# SmartMatrixSD_V1.net
KiCad netlist of a schematic drawn in EAGLE
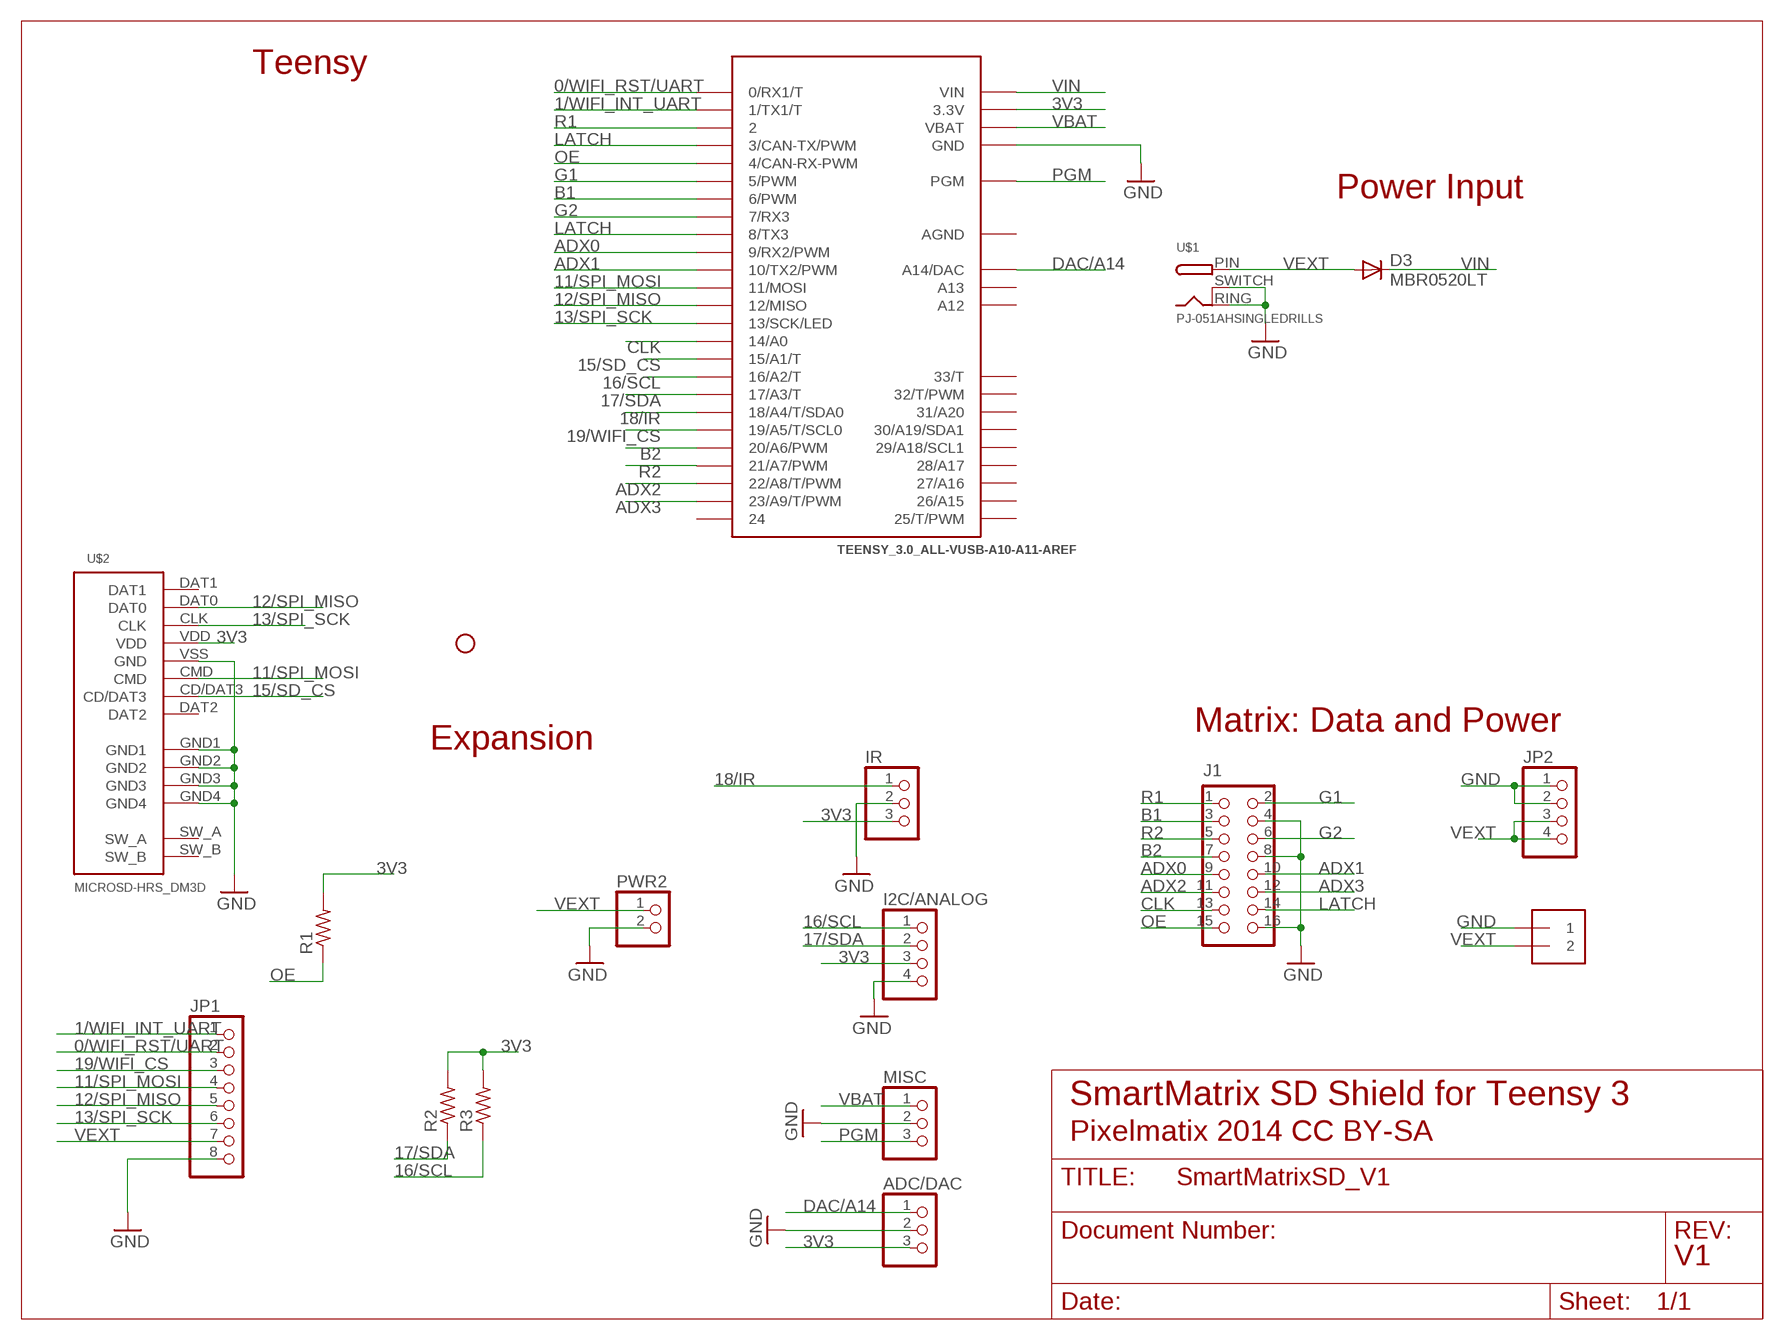
[diagram p0: schematic, sheet 1]

(export (version "E")
  (design (tool "Eeschema 10.0.6"))
  (components
    (comp (ref "ADC/DAC")
      (value "PINHD-1X03_2.54-S")
      (footprint "eagle-import:1X03-S")
      (libsource (lib "eagle-import") (part "PINHD-1X03_2.54-S"))
    )
    (comp (ref "D3")
      (value "MBR0520LT")
      (footprint "eagle-import:SOD123")
      (libsource (lib "eagle-import") (part "MBR0520LT"))
    )
    (comp (ref "I2C/ANALOG")
      (value "PINHD-1X04_2.54-S")
      (footprint "eagle-import:1X04-S")
      (libsource (lib "eagle-import") (part "pinhead-2_PINHD-1X04_2.54-S"))
    )
    (comp (ref "IR")
      (value "PINHD-1X03_2.54-S")
      (footprint "eagle-import:1X03-S")
      (libsource (lib "eagle-import") (part "PINHD-1X03_2.54-S"))
    )
    (comp (ref "J1")
      (value "CON_HEADER_2X08-PTH-SHROUDED")
      (footprint "eagle-import:PINSHRD_PTH_2X08")
      (libsource (lib "eagle-import") (part "CON_HEADER_2X08-PTH-SHROUDED"))
    )
    (comp (ref "J4")
      (value "1X2-5.0")
      (footprint "eagle-import:1X2-5.0MM")
      (libsource (lib "eagle-import") (part "1X2-5.0"))
    )
    (comp (ref "JP1")
      (value "PINHD-1X08_2.54-S")
      (footprint "eagle-import:1X08-S")
      (libsource (lib "eagle-import") (part "PINHD-1X08_2.54-S"))
    )
    (comp (ref "JP2")
      (value "PINHD-1X04_1.56")
      (footprint "eagle-import:1X04-1.56_")
      (libsource (lib "eagle-import") (part "PINHD-1X04_1.56"))
    )
    (comp (ref "JP5")
      (value "STAND-OFFSTAND-OFF-3MM")
      (footprint "eagle-import:STAND-OFF-3MM")
      (libsource (lib "eagle-import") (part "STAND-OFFSTAND-OFF-3MM"))
    )
    (comp (ref "MISC")
      (value "PINHD-1X03_2.54-S")
      (footprint "eagle-import:1X03-S")
      (libsource (lib "eagle-import") (part "PINHD-1X03_2.54-S"))
    )
    (comp (ref "PWR2")
      (value "PINHD-1X02_2.54-S")
      (footprint "eagle-import:1X02-S")
      (libsource (lib "eagle-import") (part "PINHD-1X02_2.54-S"))
    )
    (comp (ref "R1")
      (value "R-US_R0603")
      (footprint "eagle-import:R0603")
      (libsource (lib "eagle-import") (part "R-US_R0603"))
    )
    (comp (ref "R2")
      (value "R-US_0207/7")
      (footprint "eagle-import:0207_7")
      (libsource (lib "eagle-import") (part "R-US_0207/7"))
    )
    (comp (ref "R3")
      (value "R-US_0207/7")
      (footprint "eagle-import:0207_7")
      (libsource (lib "eagle-import") (part "R-US_0207/7"))
    )
    (comp (ref "U$1")
      (value "PJ-051AHSINGLEDRILLS")
      (footprint "eagle-import:PJ-051AH-SINGLEDRILLS")
      (libsource (lib "eagle-import") (part "PJ-051AHSINGLEDRILLS"))
    )
    (comp (ref "U$2")
      (value "MICROSD-HRS_DM3D")
      (footprint "eagle-import:DM3D")
      (libsource (lib "eagle-import") (part "MICROSD-HRS_DM3D"))
    )
    (comp (ref "U$3")
      (value "TEENSY_3.0_ALL-VUSB-A10-A11-AREF")
      (footprint "eagle-import:TEENSY_3.0_ALLPINS-VUSB-A11-A10-AREF")
      (libsource (lib "eagle-import") (part "TEENSY_3.0_ALL-VUSB-A10-A11-AREF"))
    )
  )
  (nets
    (net (code "1") (name "/0{slash}WIFI_RST{slash}UART") (class "Default")
      (node (ref "JP1") (pin "2") (pinfunction "2_2") (pintype "passive"))
      (node (ref "U$3") (pin "0") (pinfunction "0/RX1/T_0") (pintype "bidirectional"))
    )
    (net (code "2") (name "/1{slash}WIFI_INT_UART") (class "Default")
      (node (ref "JP1") (pin "1") (pinfunction "1_1") (pintype "passive"))
      (node (ref "U$3") (pin "1") (pinfunction "1/TX1/T_1") (pintype "bidirectional"))
    )
    (net (code "3") (name "/3V3") (class "Default")
      (node (ref "ADC/DAC") (pin "3") (pinfunction "3_3") (pintype "passive"))
      (node (ref "I2C/ANALOG") (pin "3") (pinfunction "3_3") (pintype "passive"))
      (node (ref "IR") (pin "3") (pinfunction "3_3") (pintype "passive"))
      (node (ref "R1") (pin "2") (pinfunction "2_2") (pintype "passive"))
      (node (ref "R2") (pin "2") (pinfunction "2_2") (pintype "passive"))
      (node (ref "R3") (pin "2") (pinfunction "2_2") (pintype "passive"))
      (node (ref "U$2") (pin "VDD") (pinfunction "VDD_VDD") (pintype "bidirectional"))
      (node (ref "U$3") (pin "3.3V") (pinfunction "3.3V_3.3V") (pintype "power_in"))
      (node (ref "U$3") (pin "3.3V1") (pinfunction "3.3V_3.3V1") (pintype "power_in"))
      (node (ref "U$3") (pin "3.3V2") (pinfunction "3.3V_3.3V2") (pintype "power_in"))
    )
    (net (code "4") (name "/11{slash}SPI_MOSI") (class "Default")
      (node (ref "JP1") (pin "4") (pinfunction "4_4") (pintype "passive"))
      (node (ref "U$2") (pin "CMD") (pinfunction "CMD_CMD") (pintype "bidirectional"))
      (node (ref "U$3") (pin "11") (pinfunction "11/MOSI_11") (pintype "bidirectional"))
    )
    (net (code "5") (name "/12{slash}SPI_MISO") (class "Default")
      (node (ref "JP1") (pin "5") (pinfunction "5_5") (pintype "passive"))
      (node (ref "U$2") (pin "DAT0") (pinfunction "DAT0_DAT0") (pintype "bidirectional"))
      (node (ref "U$3") (pin "12") (pinfunction "12/MISO_12") (pintype "bidirectional"))
    )
    (net (code "6") (name "/13{slash}SPI_SCK") (class "Default")
      (node (ref "JP1") (pin "6") (pinfunction "6_6") (pintype "passive"))
      (node (ref "U$2") (pin "CLK") (pinfunction "CLK_CLK") (pintype "bidirectional"))
      (node (ref "U$3") (pin "13") (pinfunction "13/SCK/LED_13") (pintype "bidirectional"))
    )
    (net (code "7") (name "/15{slash}SD_CS") (class "Default")
      (node (ref "U$2") (pin "CD/DAT3") (pinfunction "CD/DAT3_CD/DAT3") (pintype "bidirectional"))
      (node (ref "U$3") (pin "15/A1") (pinfunction "15/A1/T_15/A1") (pintype "bidirectional"))
    )
    (net (code "8") (name "/16{slash}SCL") (class "Default")
      (node (ref "I2C/ANALOG") (pin "1") (pinfunction "1_1") (pintype "passive"))
      (node (ref "R3") (pin "1") (pinfunction "1_1") (pintype "passive"))
      (node (ref "U$3") (pin "16/A2") (pinfunction "16/A2/T_16/A2") (pintype "bidirectional"))
    )
    (net (code "9") (name "/17{slash}SDA") (class "Default")
      (node (ref "I2C/ANALOG") (pin "2") (pinfunction "2_2") (pintype "passive"))
      (node (ref "R2") (pin "1") (pinfunction "1_1") (pintype "passive"))
      (node (ref "U$3") (pin "17/A3") (pinfunction "17/A3/T_17/A3") (pintype "bidirectional"))
    )
    (net (code "10") (name "/18{slash}IR") (class "Default")
      (node (ref "IR") (pin "1") (pinfunction "1_1") (pintype "passive"))
      (node (ref "U$3") (pin "18/A4") (pinfunction "18/A4/T/SDA0_18/A4") (pintype "bidirectional"))
    )
    (net (code "11") (name "/19{slash}WIFI_CS") (class "Default")
      (node (ref "JP1") (pin "3") (pinfunction "3_3") (pintype "passive"))
      (node (ref "U$3") (pin "19/A5") (pinfunction "19/A5/T/SCL0_19/A5") (pintype "bidirectional"))
    )
    (net (code "12") (name "/ADX0") (class "Default")
      (node (ref "J1") (pin "9") (pinfunction "9_9") (pintype "passive"))
      (node (ref "U$3") (pin "9") (pinfunction "9/RX2/PWM_9") (pintype "bidirectional"))
    )
    (net (code "13") (name "/ADX1") (class "Default")
      (node (ref "J1") (pin "10") (pinfunction "10_10") (pintype "passive"))
      (node (ref "U$3") (pin "10") (pinfunction "10/TX2/PWM_10") (pintype "bidirectional"))
    )
    (net (code "14") (name "/ADX2") (class "Default")
      (node (ref "J1") (pin "11") (pinfunction "11_11") (pintype "passive"))
      (node (ref "U$3") (pin "22/A8") (pinfunction "22/A8/T/PWM_22/A8") (pintype "bidirectional"))
    )
    (net (code "15") (name "/ADX3") (class "Default")
      (node (ref "J1") (pin "12") (pinfunction "12_12") (pintype "passive"))
      (node (ref "U$3") (pin "23/A9") (pinfunction "23/A9/T/PWM_23/A9") (pintype "bidirectional"))
    )
    (net (code "16") (name "/AGND") (class "Default")
      (node (ref "U$3") (pin "AGND") (pinfunction "AGND_AGND") (pintype "power_in"))
    )
    (net (code "17") (name "/B1") (class "Default")
      (node (ref "J1") (pin "3") (pinfunction "3_3") (pintype "passive"))
      (node (ref "U$3") (pin "6") (pinfunction "6/PWM_6") (pintype "bidirectional"))
    )
    (net (code "18") (name "/B2") (class "Default")
      (node (ref "J1") (pin "7") (pinfunction "7_7") (pintype "passive"))
      (node (ref "U$3") (pin "20/A6") (pinfunction "20/A6/PWM_20/A6") (pintype "bidirectional"))
    )
    (net (code "19") (name "/CLK") (class "Default")
      (node (ref "J1") (pin "13") (pinfunction "13_13") (pintype "passive"))
      (node (ref "U$3") (pin "14/A0") (pinfunction "14/A0_14/A0") (pintype "bidirectional"))
    )
    (net (code "20") (name "/DAC{slash}A14") (class "Default")
      (node (ref "ADC/DAC") (pin "1") (pinfunction "1_1") (pintype "passive"))
      (node (ref "U$3") (pin "RESET") (pinfunction "A14/DAC_RESET") (pintype "bidirectional"))
    )
    (net (code "21") (name "/G1") (class "Default")
      (node (ref "J1") (pin "2") (pinfunction "2_2") (pintype "passive"))
      (node (ref "U$3") (pin "5") (pinfunction "5/PWM_5") (pintype "bidirectional"))
    )
    (net (code "22") (name "/G2") (class "Default")
      (node (ref "J1") (pin "6") (pinfunction "6_6") (pintype "passive"))
      (node (ref "U$3") (pin "7") (pinfunction "7/RX3_7") (pintype "bidirectional"))
    )
    (net (code "23") (name "/LATCH") (class "Default")
      (node (ref "J1") (pin "14") (pinfunction "14_14") (pintype "passive"))
      (node (ref "U$3") (pin "3") (pinfunction "3/CAN-TX/PWM_3") (pintype "bidirectional"))
      (node (ref "U$3") (pin "8") (pinfunction "8/TX3_8") (pintype "bidirectional"))
    )
    (net (code "24") (name "/OE") (class "Default")
      (node (ref "J1") (pin "15") (pinfunction "15_15") (pintype "passive"))
      (node (ref "R1") (pin "1") (pinfunction "1_1") (pintype "passive"))
      (node (ref "U$3") (pin "4") (pinfunction "4/CAN-RX-PWM_4") (pintype "bidirectional"))
    )
    (net (code "25") (name "/PGM") (class "Default")
      (node (ref "MISC") (pin "3") (pinfunction "3_3") (pintype "passive"))
      (node (ref "U$3") (pin "PGM") (pinfunction "PGM_PGM") (pintype "bidirectional"))
    )
    (net (code "26") (name "/R1") (class "Default")
      (node (ref "J1") (pin "1") (pinfunction "1_1") (pintype "passive"))
      (node (ref "U$3") (pin "2") (pinfunction "2_2") (pintype "bidirectional"))
    )
    (net (code "27") (name "/R2") (class "Default")
      (node (ref "J1") (pin "5") (pinfunction "5_5") (pintype "passive"))
      (node (ref "U$3") (pin "21/A7") (pinfunction "21/A7/PWM_21/A7") (pintype "bidirectional"))
    )
    (net (code "28") (name "/VBAT") (class "Default")
      (node (ref "MISC") (pin "1") (pinfunction "1_1") (pintype "passive"))
      (node (ref "U$3") (pin "VBAT") (pinfunction "VBAT_VBAT") (pintype "power_in"))
    )
    (net (code "29") (name "/VEXT") (class "Default")
      (node (ref "D3") (pin "A") (pinfunction "A_A") (pintype "passive"))
      (node (ref "J4") (pin "2") (pinfunction "2_2") (pintype "passive"))
      (node (ref "JP1") (pin "7") (pinfunction "7_7") (pintype "passive"))
      (node (ref "JP2") (pin "3") (pinfunction "3_3") (pintype "passive"))
      (node (ref "JP2") (pin "4") (pinfunction "4_4") (pintype "passive"))
      (node (ref "PWR2") (pin "1") (pinfunction "1_1") (pintype "passive"))
      (node (ref "U$1") (pin "PIN") (pinfunction "PWR_PIN") (pintype "power_in"))
    )
    (net (code "30") (name "/VIN") (class "Default")
      (node (ref "D3") (pin "C") (pinfunction "C_C") (pintype "passive"))
      (node (ref "U$3") (pin "VIN") (pinfunction "VIN_VIN") (pintype "power_in"))
    )
    (net (code "31") (name "GND") (class "Default")
      (node (ref "ADC/DAC") (pin "2") (pinfunction "2_2") (pintype "passive"))
      (node (ref "I2C/ANALOG") (pin "4") (pinfunction "4_4") (pintype "passive"))
      (node (ref "IR") (pin "2") (pinfunction "2_2") (pintype "passive"))
      (node (ref "J1") (pin "16") (pinfunction "16_16") (pintype "passive"))
      (node (ref "J1") (pin "4") (pinfunction "4_4") (pintype "passive"))
      (node (ref "J1") (pin "8") (pinfunction "8_8") (pintype "passive"))
      (node (ref "J4") (pin "1") (pinfunction "1_1") (pintype "passive"))
      (node (ref "JP1") (pin "8") (pinfunction "8_8") (pintype "passive"))
      (node (ref "JP2") (pin "1") (pinfunction "1_1") (pintype "passive"))
      (node (ref "JP2") (pin "2") (pinfunction "2_2") (pintype "passive"))
      (node (ref "MISC") (pin "2") (pinfunction "2_2") (pintype "passive"))
      (node (ref "PWR2") (pin "2") (pinfunction "2_2") (pintype "passive"))
      (node (ref "U$1") (pin "RING") (pinfunction "GND_RING") (pintype "power_in"))
      (node (ref "U$1") (pin "SWITCH") (pinfunction "GNDBREAK_SWITCH") (pintype "power_in"))
      (node (ref "U$2") (pin "GND1") (pinfunction "GND1_GND1") (pintype "bidirectional"))
      (node (ref "U$2") (pin "GND2") (pinfunction "GND2_GND2") (pintype "bidirectional"))
      (node (ref "U$2") (pin "GND3") (pinfunction "GND3_GND3") (pintype "bidirectional"))
      (node (ref "U$2") (pin "GND4") (pinfunction "GND4_GND4") (pintype "bidirectional"))
      (node (ref "U$2") (pin "VSS") (pinfunction "GND_VSS") (pintype "bidirectional"))
      (node (ref "U$3") (pin "GND") (pinfunction "GND_GND") (pintype "power_in"))
      (node (ref "U$3") (pin "GND1") (pinfunction "GND_GND1") (pintype "power_in"))
      (node (ref "U$3") (pin "GND2") (pinfunction "GND_GND2") (pintype "power_in"))
    )
    (net (code "32") (name "unconnected-(U$2-PadDAT1)") (class "Default")
      (node (ref "U$2") (pin "DAT1") (pinfunction "DAT1_DAT1") (pintype "bidirectional"))
    )
    (net (code "33") (name "unconnected-(U$2-PadDAT2)") (class "Default")
      (node (ref "U$2") (pin "DAT2") (pinfunction "DAT2_DAT2") (pintype "bidirectional"))
    )
    (net (code "34") (name "unconnected-(U$2-PadSW_A)") (class "Default")
      (node (ref "U$2") (pin "SW_A") (pinfunction "SW_A_SW_A") (pintype "bidirectional"))
    )
    (net (code "35") (name "unconnected-(U$2-PadSW_B)") (class "Default")
      (node (ref "U$2") (pin "SW_B") (pinfunction "SW_B_SW_B") (pintype "bidirectional"))
    )
    (net (code "36") (name "unconnected-(U$3-25{slash}T{slash}PWM-Pad25)") (class "Default")
      (node (ref "U$3") (pin "25") (pinfunction "25/T/PWM_25") (pintype "bidirectional"))
    )
    (net (code "37") (name "unconnected-(U$3-26{slash}A15-Pad26)") (class "Default")
      (node (ref "U$3") (pin "26") (pinfunction "26/A15_26") (pintype "bidirectional"))
    )
    (net (code "38") (name "unconnected-(U$3-27{slash}A16-Pad27)") (class "Default")
      (node (ref "U$3") (pin "27") (pinfunction "27/A16_27") (pintype "bidirectional"))
    )
    (net (code "39") (name "unconnected-(U$3-28{slash}A17-Pad28)") (class "Default")
      (node (ref "U$3") (pin "28") (pinfunction "28/A17_28") (pintype "bidirectional"))
    )
    (net (code "40") (name "unconnected-(U$3-29{slash}A18{slash}SCL1-Pad29)") (class "Default")
      (node (ref "U$3") (pin "29") (pinfunction "29/A18/SCL1_29") (pintype "bidirectional"))
    )
    (net (code "41") (name "unconnected-(U$3-30{slash}A19{slash}SDA1-Pad30)") (class "Default")
      (node (ref "U$3") (pin "30") (pinfunction "30/A19/SDA1_30") (pintype "bidirectional"))
    )
    (net (code "42") (name "unconnected-(U$3-31{slash}A20-Pad31)") (class "Default")
      (node (ref "U$3") (pin "31") (pinfunction "31/A20_31") (pintype "bidirectional"))
    )
    (net (code "43") (name "unconnected-(U$3-32{slash}T{slash}PWM-Pad32)") (class "Default")
      (node (ref "U$3") (pin "32") (pinfunction "32/T/PWM_32") (pintype "bidirectional"))
    )
    (net (code "44") (name "unconnected-(U$3-33{slash}T-Pad33)") (class "Default")
      (node (ref "U$3") (pin "33") (pinfunction "33/T_33") (pintype "bidirectional"))
    )
    (net (code "45") (name "unconnected-(U$3-Pad24)") (class "Default")
      (node (ref "U$3") (pin "24") (pinfunction "24_24") (pintype "bidirectional"))
    )
    (net (code "46") (name "unconnected-(U$3-PadA12)") (class "Default")
      (node (ref "U$3") (pin "A12") (pinfunction "A12_A12") (pintype "bidirectional"))
    )
    (net (code "47") (name "unconnected-(U$3-PadA13)") (class "Default")
      (node (ref "U$3") (pin "A13") (pinfunction "A13_A13") (pintype "bidirectional"))
    )
  )
)
